# X-ADE-12MH.net
KiCad netlist of a schematic drawn in Altium Designer
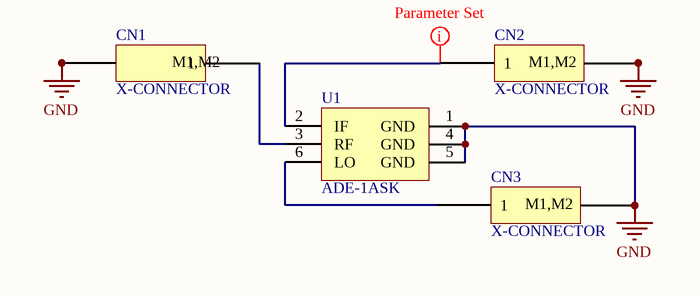
[diagram p0: X-ADE-12MH+.SchDoc]

(export (version "E")
  (design (tool "Eeschema 10.0.6"))
  (components
    (comp (ref "CN1")
      (value "X-CONNECTOR")
      (footprint "X-CONNECTOR-PCB")
      (description "CONECTOR PARA MÓDULOS X MICROWAVE")
      (libsource (lib "") (part "X-CONNECTOR_1"))
    )
    (comp (ref "CN2")
      (value "X-CONNECTOR")
      (footprint "X-CONNECTOR-PCB")
      (description "CONECTOR PARA MÓDULOS X MICROWAVE")
      (libsource (lib "(LR)²") (part "X-CONNECTOR"))
    )
    (comp (ref "CN3")
      (value "X-CONNECTOR")
      (footprint "X-CONNECTOR-PCB")
      (description "CONECTOR PARA MÓDULOS X MICROWAVE")
      (libsource (lib "(LR)²") (part "X-CONNECTOR"))
    )
    (comp (ref "U1")
      (value "ADE-1ASK")
      (footprint "MINI-CD542-6_V")
      (fields (field (name "MANUFACTURER") "Mini-Circuits"))
      (libsource (lib "Altium Content Vault") (part "MINI-ADE-1ASK-CD542-6"))
    )
  )
  (nets
    (net (code "1") (name "GND") (class "Default")
      (node (ref "CN1") (pin "M1") (pinfunction "M1_M1") (pintype "passive"))
      (node (ref "CN1") (pin "M2") (pinfunction "M2_M2") (pintype "passive"))
      (node (ref "CN2") (pin "M1") (pinfunction "M1_M1") (pintype "passive"))
      (node (ref "CN2") (pin "M2") (pinfunction "M2_M2") (pintype "passive"))
      (node (ref "CN3") (pin "M1") (pinfunction "M1_M1") (pintype "passive"))
      (node (ref "CN3") (pin "M2") (pinfunction "M2_M2") (pintype "passive"))
      (node (ref "U1") (pin "1") (pinfunction "GND_1") (pintype "power_in"))
      (node (ref "U1") (pin "4") (pinfunction "GND_4") (pintype "power_in"))
      (node (ref "U1") (pin "5") (pinfunction "GND_5") (pintype "power_in"))
    )
    (net (code "2") (name "Net-(U1-IF)") (class "Default")
      (node (ref "CN2") (pin "1") (pinfunction "1_1") (pintype "passive"))
      (node (ref "U1") (pin "2") (pinfunction "IF_2") (pintype "passive"))
    )
    (net (code "3") (name "Net-(U1-LO)") (class "Default")
      (node (ref "CN3") (pin "1") (pinfunction "1_1") (pintype "passive"))
      (node (ref "U1") (pin "6") (pinfunction "LO_6") (pintype "passive"))
    )
    (net (code "4") (name "Net-(U1-RF)") (class "Default")
      (node (ref "CN1") (pin "1") (pinfunction "1_1") (pintype "passive"))
      (node (ref "U1") (pin "3") (pinfunction "RF_3") (pintype "passive"))
    )
  )
)
